# DAU_Kupplung_3phasig_V1_6.net
KiCad netlist of a schematic drawn in EAGLE
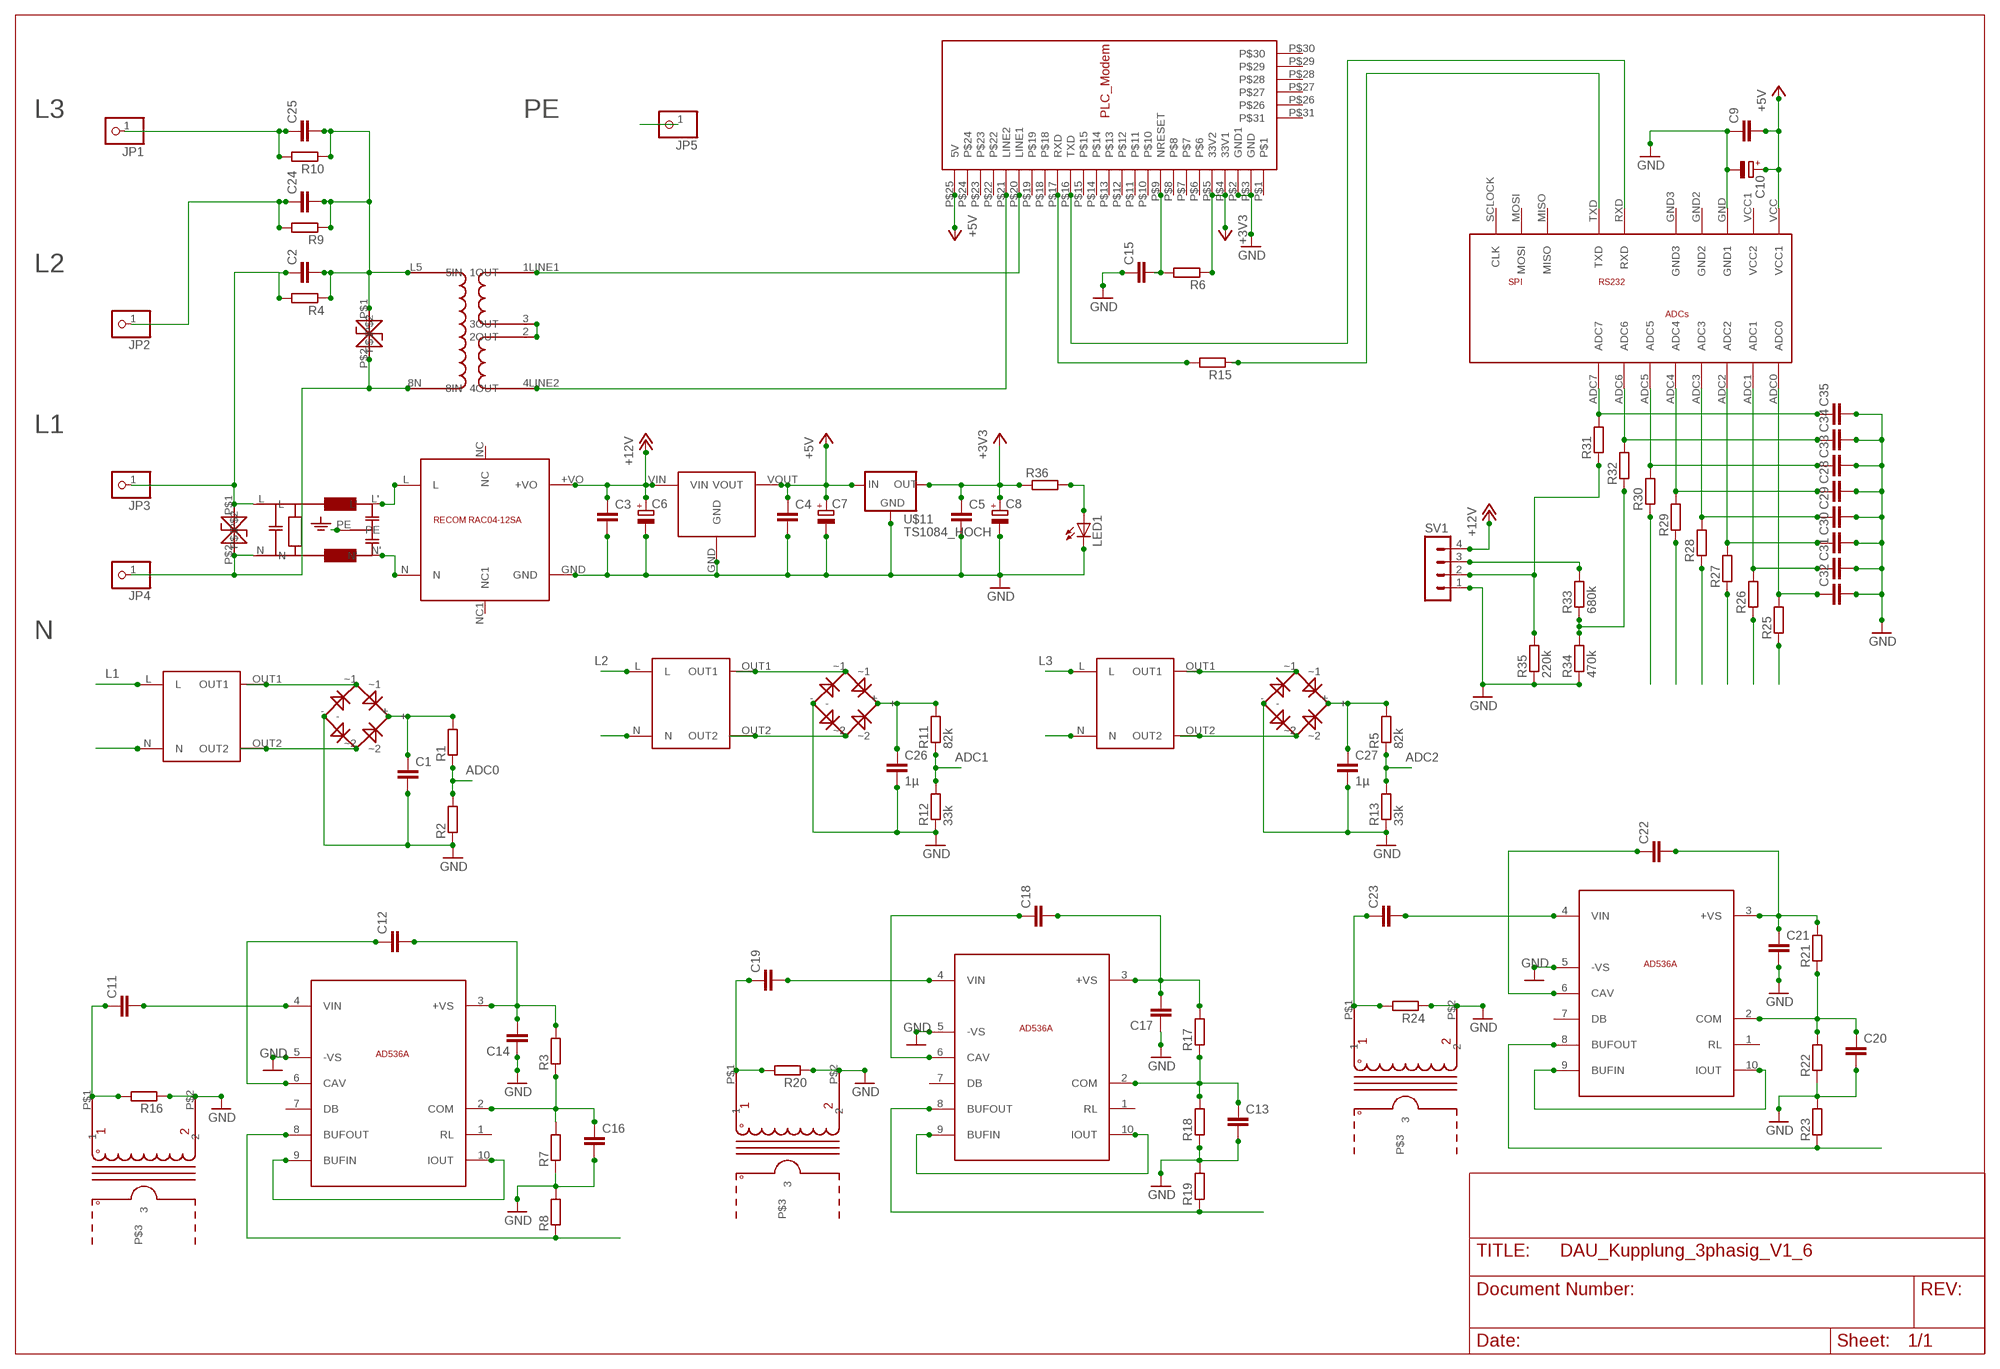
[diagram p0: schematic, sheet 1]

(export (version "E")
  (design (tool "Eeschema 10.0.6"))
  (components
    (comp (ref "AC1002_1")
      (value "AC1010")
      (footprint "eagle-import:AC1010")
      (libsource (lib "eagle-import") (part "AC1010"))
    )
    (comp (ref "C1")
      (value "C-EUC0805K")
      (footprint "eagle-import:C0805K")
      (libsource (lib "eagle-import") (part "C-EUC0805K"))
    )
    (comp (ref "C2")
      (value "C-EU225-087X268")
      (footprint "eagle-import:C225-087X268")
      (libsource (lib "eagle-import") (part "C-EU225-087X268"))
    )
    (comp (ref "C3")
      (value "C-EUC0805K")
      (footprint "eagle-import:C0805K")
      (libsource (lib "eagle-import") (part "C-EUC0805K"))
    )
    (comp (ref "C4")
      (value "C-EUC0805K")
      (footprint "eagle-import:C0805K")
      (libsource (lib "eagle-import") (part "C-EUC0805K"))
    )
    (comp (ref "C5")
      (value "C-EUC0805K")
      (footprint "eagle-import:C0805K")
      (libsource (lib "eagle-import") (part "C-EUC0805K"))
    )
    (comp (ref "C6")
      (value "CPOL-EUE2.5-6")
      (footprint "eagle-import:E2,5-6")
      (libsource (lib "eagle-import") (part "resistor_CPOL-EUE2.5-6"))
    )
    (comp (ref "C7")
      (value "CPOL-EUE2.5-6")
      (footprint "eagle-import:E2,5-6")
      (libsource (lib "eagle-import") (part "resistor_CPOL-EUE2.5-6"))
    )
    (comp (ref "C8")
      (value "CPOL-EUE2.5-6")
      (footprint "eagle-import:E2,5-6")
      (libsource (lib "eagle-import") (part "resistor_CPOL-EUE2.5-6"))
    )
    (comp (ref "C9")
      (value "C-EUC0805K")
      (footprint "eagle-import:C0805K")
      (libsource (lib "eagle-import") (part "C-EUC0805K"))
    )
    (comp (ref "C10")
      (value "CPOL-EUE2,5-6E")
      (footprint "eagle-import:E2,5-6E")
      (libsource (lib "eagle-import") (part "CPOL-EUE2,5-6E"))
    )
    (comp (ref "C11")
      (value "C-EUC0805K")
      (footprint "eagle-import:C0805K")
      (libsource (lib "eagle-import") (part "C-EUC0805K"))
    )
    (comp (ref "C12")
      (value "C-EUC0805K")
      (footprint "eagle-import:C0805K")
      (libsource (lib "eagle-import") (part "C-EUC0805K"))
    )
    (comp (ref "C13")
      (value "C-EUC0805K")
      (footprint "eagle-import:C0805K")
      (libsource (lib "eagle-import") (part "C-EUC0805K"))
    )
    (comp (ref "C14")
      (value "C-EUC0805K")
      (footprint "eagle-import:C0805K")
      (libsource (lib "eagle-import") (part "C-EUC0805K"))
    )
    (comp (ref "C15")
      (value "C-EUC0805K")
      (footprint "eagle-import:C0805K")
      (libsource (lib "eagle-import") (part "C-EUC0805K"))
    )
    (comp (ref "C16")
      (value "C-EUC0805K")
      (footprint "eagle-import:C0805K")
      (libsource (lib "eagle-import") (part "C-EUC0805K"))
    )
    (comp (ref "C17")
      (value "C-EUC0805K")
      (footprint "eagle-import:C0805K")
      (libsource (lib "eagle-import") (part "C-EUC0805K"))
    )
    (comp (ref "C18")
      (value "C-EUC0805K")
      (footprint "eagle-import:C0805K")
      (libsource (lib "eagle-import") (part "C-EUC0805K"))
    )
    (comp (ref "C19")
      (value "C-EUC0805K")
      (footprint "eagle-import:C0805K")
      (libsource (lib "eagle-import") (part "C-EUC0805K"))
    )
    (comp (ref "C20")
      (value "C-EUC0805K")
      (footprint "eagle-import:C0805K")
      (libsource (lib "eagle-import") (part "C-EUC0805K"))
    )
    (comp (ref "C21")
      (value "C-EUC0805K")
      (footprint "eagle-import:C0805K")
      (libsource (lib "eagle-import") (part "C-EUC0805K"))
    )
    (comp (ref "C22")
      (value "C-EUC0805K")
      (footprint "eagle-import:C0805K")
      (libsource (lib "eagle-import") (part "C-EUC0805K"))
    )
    (comp (ref "C23")
      (value "C-EUC0805K")
      (footprint "eagle-import:C0805K")
      (libsource (lib "eagle-import") (part "C-EUC0805K"))
    )
    (comp (ref "C24")
      (value "C-EU225-087X268")
      (footprint "eagle-import:C225-087X268")
      (libsource (lib "eagle-import") (part "C-EU225-087X268"))
    )
    (comp (ref "C25")
      (value "C-EU225-087X268")
      (footprint "eagle-import:C225-087X268")
      (libsource (lib "eagle-import") (part "C-EU225-087X268"))
    )
    (comp (ref "C26")
      (value "1µ")
      (footprint "eagle-import:C0805K")
      (libsource (lib "eagle-import") (part "C-EUC0805K"))
    )
    (comp (ref "C27")
      (value "1µ")
      (footprint "eagle-import:C0805K")
      (libsource (lib "eagle-import") (part "C-EUC0805K"))
    )
    (comp (ref "C28")
      (value "C-EUC0805K")
      (footprint "eagle-import:C0805K")
      (libsource (lib "eagle-import") (part "C-EUC0805K"))
    )
    (comp (ref "C29")
      (value "C-EUC0805K")
      (footprint "eagle-import:C0805K")
      (libsource (lib "eagle-import") (part "C-EUC0805K"))
    )
    (comp (ref "C30")
      (value "C-EUC0805K")
      (footprint "eagle-import:C0805K")
      (libsource (lib "eagle-import") (part "C-EUC0805K"))
    )
    (comp (ref "C31")
      (value "C-EUC0805K")
      (footprint "eagle-import:C0805K")
      (libsource (lib "eagle-import") (part "C-EUC0805K"))
    )
    (comp (ref "C32")
      (value "C-EUC0805K")
      (footprint "eagle-import:C0805K")
      (libsource (lib "eagle-import") (part "C-EUC0805K"))
    )
    (comp (ref "C33")
      (value "C-EUC0805K")
      (footprint "eagle-import:C0805K")
      (libsource (lib "eagle-import") (part "C-EUC0805K"))
    )
    (comp (ref "C34")
      (value "C-EUC0805K")
      (footprint "eagle-import:C0805K")
      (libsource (lib "eagle-import") (part "C-EUC0805K"))
    )
    (comp (ref "C35")
      (value "C-EUC0805K")
      (footprint "eagle-import:C0805K")
      (libsource (lib "eagle-import") (part "C-EUC0805K"))
    )
    (comp (ref "JP1")
      (value "PINHD-1X1")
      (footprint "eagle-import:1X01")
      (libsource (lib "eagle-import") (part "PINHD-1X1"))
    )
    (comp (ref "JP2")
      (value "PINHD-1X1")
      (footprint "eagle-import:1X01")
      (libsource (lib "eagle-import") (part "PINHD-1X1"))
    )
    (comp (ref "JP3")
      (value "PINHD-1X1")
      (footprint "eagle-import:1X01")
      (libsource (lib "eagle-import") (part "PINHD-1X1"))
    )
    (comp (ref "JP4")
      (value "PINHD-1X1")
      (footprint "eagle-import:1X01")
      (libsource (lib "eagle-import") (part "PINHD-1X1"))
    )
    (comp (ref "JP5")
      (value "PINHD-1X1")
      (footprint "eagle-import:1X01")
      (libsource (lib "eagle-import") (part "PINHD-1X1"))
    )
    (comp (ref "LED1")
      (value "LEDSQR2X5")
      (footprint "eagle-import:LED2X5")
      (libsource (lib "eagle-import") (part "LEDSQR2X5"))
    )
    (comp (ref "R1")
      (value "R-EU_R0805")
      (footprint "eagle-import:R0805")
      (libsource (lib "eagle-import") (part "R-EU_R0805"))
    )
    (comp (ref "R2")
      (value "R-EU_R0805")
      (footprint "eagle-import:R0805")
      (libsource (lib "eagle-import") (part "R-EU_R0805"))
    )
    (comp (ref "R3")
      (value "R-EU_R0805")
      (footprint "eagle-import:R0805")
      (libsource (lib "eagle-import") (part "R-EU_R0805"))
    )
    (comp (ref "R4")
      (value "R-EU_0204/7")
      (footprint "eagle-import:0204_7")
      (libsource (lib "eagle-import") (part "R-EU_0204/7"))
    )
    (comp (ref "R5")
      (value "82k")
      (footprint "eagle-import:R0805")
      (libsource (lib "eagle-import") (part "R-EU_R0805"))
    )
    (comp (ref "R6")
      (value "R-EU_R0805")
      (footprint "eagle-import:R0805")
      (libsource (lib "eagle-import") (part "R-EU_R0805"))
    )
    (comp (ref "R7")
      (value "R-EU_R0805")
      (footprint "eagle-import:R0805")
      (libsource (lib "eagle-import") (part "R-EU_R0805"))
    )
    (comp (ref "R8")
      (value "R-EU_R0805")
      (footprint "eagle-import:R0805")
      (libsource (lib "eagle-import") (part "R-EU_R0805"))
    )
    (comp (ref "R9")
      (value "R-EU_0204/7")
      (footprint "eagle-import:0204_7")
      (libsource (lib "eagle-import") (part "R-EU_0204/7"))
    )
    (comp (ref "R10")
      (value "R-EU_0204/7")
      (footprint "eagle-import:0204_7")
      (libsource (lib "eagle-import") (part "R-EU_0204/7"))
    )
    (comp (ref "R11")
      (value "82k")
      (footprint "eagle-import:R0805")
      (libsource (lib "eagle-import") (part "R-EU_R0805"))
    )
    (comp (ref "R12")
      (value "33k")
      (footprint "eagle-import:R0805")
      (libsource (lib "eagle-import") (part "R-EU_R0805"))
    )
    (comp (ref "R13")
      (value "33k")
      (footprint "eagle-import:R0805")
      (libsource (lib "eagle-import") (part "R-EU_R0805"))
    )
    (comp (ref "R15")
      (value "R-EU_R0805")
      (footprint "eagle-import:R0805")
      (libsource (lib "eagle-import") (part "R-EU_R0805"))
    )
    (comp (ref "R16")
      (value "R-EU_0204/7")
      (footprint "eagle-import:0204_7")
      (libsource (lib "eagle-import") (part "R-EU_0204/7"))
    )
    (comp (ref "R17")
      (value "R-EU_R0805")
      (footprint "eagle-import:R0805")
      (libsource (lib "eagle-import") (part "R-EU_R0805"))
    )
    (comp (ref "R18")
      (value "R-EU_R0805")
      (footprint "eagle-import:R0805")
      (libsource (lib "eagle-import") (part "R-EU_R0805"))
    )
    (comp (ref "R19")
      (value "R-EU_R0805")
      (footprint "eagle-import:R0805")
      (libsource (lib "eagle-import") (part "R-EU_R0805"))
    )
    (comp (ref "R20")
      (value "R-EU_0204/7")
      (footprint "eagle-import:0204_7")
      (libsource (lib "eagle-import") (part "R-EU_0204/7"))
    )
    (comp (ref "R21")
      (value "R-EU_R0805")
      (footprint "eagle-import:R0805")
      (libsource (lib "eagle-import") (part "R-EU_R0805"))
    )
    (comp (ref "R22")
      (value "R-EU_R0805")
      (footprint "eagle-import:R0805")
      (libsource (lib "eagle-import") (part "R-EU_R0805"))
    )
    (comp (ref "R23")
      (value "R-EU_R0805")
      (footprint "eagle-import:R0805")
      (libsource (lib "eagle-import") (part "R-EU_R0805"))
    )
    (comp (ref "R24")
      (value "R-EU_0204/7")
      (footprint "eagle-import:0204_7")
      (libsource (lib "eagle-import") (part "R-EU_0204/7"))
    )
    (comp (ref "R25")
      (value "R-EU_R0805")
      (footprint "eagle-import:R0805")
      (libsource (lib "eagle-import") (part "R-EU_R0805"))
    )
    (comp (ref "R26")
      (value "R-EU_R0805")
      (footprint "eagle-import:R0805")
      (libsource (lib "eagle-import") (part "R-EU_R0805"))
    )
    (comp (ref "R27")
      (value "R-EU_R0805")
      (footprint "eagle-import:R0805")
      (libsource (lib "eagle-import") (part "R-EU_R0805"))
    )
    (comp (ref "R28")
      (value "R-EU_R0805")
      (footprint "eagle-import:R0805")
      (libsource (lib "eagle-import") (part "R-EU_R0805"))
    )
    (comp (ref "R29")
      (value "R-EU_R0805")
      (footprint "eagle-import:R0805")
      (libsource (lib "eagle-import") (part "R-EU_R0805"))
    )
    (comp (ref "R30")
      (value "R-EU_R0805")
      (footprint "eagle-import:R0805")
      (libsource (lib "eagle-import") (part "R-EU_R0805"))
    )
    (comp (ref "R31")
      (value "R-EU_R0805")
      (footprint "eagle-import:R0805")
      (libsource (lib "eagle-import") (part "R-EU_R0805"))
    )
    (comp (ref "R32")
      (value "R-EU_R0805")
      (footprint "eagle-import:R0805")
      (libsource (lib "eagle-import") (part "R-EU_R0805"))
    )
    (comp (ref "R33")
      (value "680k")
      (footprint "eagle-import:R0805")
      (libsource (lib "eagle-import") (part "R-EU_R0805"))
    )
    (comp (ref "R34")
      (value "470k")
      (footprint "eagle-import:R0805")
      (libsource (lib "eagle-import") (part "R-EU_R0805"))
    )
    (comp (ref "R35")
      (value "220k")
      (footprint "eagle-import:R0805")
      (libsource (lib "eagle-import") (part "R-EU_R0805"))
    )
    (comp (ref "R36")
      (value "R-EU_R0805")
      (footprint "eagle-import:R0805")
      (libsource (lib "eagle-import") (part "R-EU_R0805"))
    )
    (comp (ref "SV1")
      (value "MA04-1")
      (footprint "eagle-import:MA04-1")
      (libsource (lib "eagle-import") (part "MA04-1"))
    )
    (comp (ref "TSV1")
      (value "TSV")
      (footprint "eagle-import:TSV")
      (libsource (lib "eagle-import") (part "TSV"))
    )
    (comp (ref "TSV2")
      (value "TSV")
      (footprint "eagle-import:TSV")
      (libsource (lib "eagle-import") (part "TSV"))
    )
    (comp (ref "U$1")
      (value "RECOM_RAC04_12SA")
      (footprint "eagle-import:RAC04_12SA")
      (libsource (lib "eagle-import") (part "RECOM_RAC04_12SA"))
    )
    (comp (ref "U$2")
      (value "SICHERHEITSTRAFO")
      (footprint "eagle-import:TRAFO_0,35VA")
      (libsource (lib "eagle-import") (part "SICHERHEITSTRAFO"))
    )
    (comp (ref "U$3")
      (value "ADUC831_MINIMUM")
      (footprint "eagle-import:ADUC_MINIMUM")
      (libsource (lib "eagle-import") (part "ADUC831_MINIMUM"))
    )
    (comp (ref "U$4")
      (value "MODEMSTECKER")
      (footprint "eagle-import:MODEM_FUSS")
      (libsource (lib "eagle-import") (part "MODEMSTECKER"))
    )
    (comp (ref "U$5")
      (value "PLC_UEBERTRAGER_V2")
      (footprint "eagle-import:PLC-UEBERTRAGER_V2")
      (libsource (lib "eagle-import") (part "PLC_UEBERTRAGER_V2"))
    )
    (comp (ref "U$7")
      (value "AC1010")
      (footprint "eagle-import:AC1010")
      (libsource (lib "eagle-import") (part "AC1010"))
    )
    (comp (ref "U$8")
      (value "RECTIFIER")
      (footprint "eagle-import:RECTIFIER")
      (libsource (lib "eagle-import") (part "RECTIFIER"))
    )
    (comp (ref "U$10")
      (value "RECOM_785_05")
      (footprint "eagle-import:RECOM785X")
      (libsource (lib "eagle-import") (part "RECOM_785_05"))
    )
    (comp (ref "U$11")
      (value "TS1084_HOCH")
      (footprint "eagle-import:TS1084_HOCH")
      (libsource (lib "eagle-import") (part "TS1084_HOCH"))
    )
    (comp (ref "U$12")
      (value "AD536")
      (footprint "eagle-import:TO100_10PIN")
      (libsource (lib "eagle-import") (part "AD536"))
    )
    (comp (ref "U$13")
      (value "AD536")
      (footprint "eagle-import:TO100_10PIN")
      (libsource (lib "eagle-import") (part "AD536"))
    )
    (comp (ref "U$14")
      (value "AC1010")
      (footprint "eagle-import:AC1010")
      (libsource (lib "eagle-import") (part "AC1010"))
    )
    (comp (ref "U$15")
      (value "AD536")
      (footprint "eagle-import:TO100_10PIN")
      (libsource (lib "eagle-import") (part "AD536"))
    )
    (comp (ref "U$16")
      (value "SICHERHEITSTRAFO")
      (footprint "eagle-import:TRAFO_0,35VA")
      (libsource (lib "eagle-import") (part "SICHERHEITSTRAFO"))
    )
    (comp (ref "U$17")
      (value "RECTIFIER")
      (footprint "eagle-import:RECTIFIER")
      (libsource (lib "eagle-import") (part "RECTIFIER"))
    )
    (comp (ref "U$18")
      (value "SICHERHEITSTRAFO")
      (footprint "eagle-import:TRAFO_0,35VA")
      (libsource (lib "eagle-import") (part "SICHERHEITSTRAFO"))
    )
    (comp (ref "U$19")
      (value "RECTIFIER")
      (footprint "eagle-import:RECTIFIER")
      (libsource (lib "eagle-import") (part "RECTIFIER"))
    )
    (comp (ref "U$20")
      (value "NETZFILTER_05_A")
      (footprint "eagle-import:NETZFILTER")
      (libsource (lib "eagle-import") (part "NETZFILTER_05_A"))
    )
  )
  (nets
    (net (code "1") (name "+3V3") (class "Default")
      (node (ref "C5") (pin "1") (pinfunction "1_1") (pintype "passive"))
      (node (ref "C8") (pin "+") (pinfunction "+_+") (pintype "passive"))
      (node (ref "R36") (pin "1") (pinfunction "1_1") (pintype "passive"))
      (node (ref "R6") (pin "1") (pinfunction "1_1") (pintype "passive"))
      (node (ref "U$11") (pin "OUT") (pinfunction "OUT_OUT") (pintype "passive"))
      (node (ref "U$4") (pin "P$4") (pinfunction "33V1_P$4") (pintype "bidirectional"))
      (node (ref "U$4") (pin "P$5") (pinfunction "33V2_P$5") (pintype "bidirectional"))
    )
    (net (code "2") (name "+5V") (class "Default")
      (node (ref "C10") (pin "+") (pinfunction "+_+") (pintype "passive"))
      (node (ref "C4") (pin "1") (pinfunction "1_1") (pintype "passive"))
      (node (ref "C7") (pin "+") (pinfunction "+_+") (pintype "passive"))
      (node (ref "C9") (pin "2") (pinfunction "2_2") (pintype "passive"))
      (node (ref "U$10") (pin "VOUT") (pinfunction "VOUT_VOUT") (pintype "bidirectional"))
      (node (ref "U$11") (pin "IN") (pinfunction "IN_IN") (pintype "input"))
      (node (ref "U$3") (pin "VCC") (pinfunction "VCC1_VCC") (pintype "bidirectional"))
      (node (ref "U$4") (pin "P$25") (pinfunction "5V_P$25") (pintype "bidirectional"))
    )
    (net (code "3") (name "+12V") (class "Default")
      (node (ref "C3") (pin "1") (pinfunction "1_1") (pintype "passive"))
      (node (ref "C6") (pin "+") (pinfunction "+_+") (pintype "passive"))
      (node (ref "SV1") (pin "4") (pinfunction "4_4") (pintype "passive"))
      (node (ref "U$1") (pin "+VO") (pinfunction "+VO_+VO") (pintype "bidirectional"))
      (node (ref "U$10") (pin "VIN") (pinfunction "VIN_VIN") (pintype "bidirectional"))
    )
    (net (code "4") (name "/I1") (class "Default")
      (node (ref "R28") (pin "1") (pinfunction "1_1") (pintype "passive"))
      (node (ref "R8") (pin "1") (pinfunction "1_1") (pintype "passive"))
      (node (ref "U$13") (pin "8") (pinfunction "BUFOUT_8") (pintype "bidirectional"))
    )
    (net (code "5") (name "/I2") (class "Default")
      (node (ref "R19") (pin "1") (pinfunction "1_1") (pintype "passive"))
      (node (ref "R29") (pin "1") (pinfunction "1_1") (pintype "passive"))
      (node (ref "U$12") (pin "8") (pinfunction "BUFOUT_8") (pintype "bidirectional"))
    )
    (net (code "6") (name "/I3") (class "Default")
      (node (ref "R23") (pin "1") (pinfunction "1_1") (pintype "passive"))
      (node (ref "R30") (pin "1") (pinfunction "1_1") (pintype "passive"))
      (node (ref "U$15") (pin "8") (pinfunction "BUFOUT_8") (pintype "bidirectional"))
    )
    (net (code "7") (name "/L1") (class "Default")
      (node (ref "C2") (pin "1") (pinfunction "1_1") (pintype "passive"))
      (node (ref "JP3") (pin "1") (pinfunction "1_1") (pintype "passive"))
      (node (ref "R4") (pin "2") (pinfunction "2_2") (pintype "passive"))
      (node (ref "TSV1") (pin "P$1") (pinfunction "P$1_P$1") (pintype "bidirectional"))
      (node (ref "U$2") (pin "L") (pinfunction "L_L") (pintype "bidirectional"))
      (node (ref "U$20") (pin "L") (pinfunction "L_L") (pintype "bidirectional"))
    )
    (net (code "8") (name "/L2") (class "Default")
      (node (ref "C24") (pin "1") (pinfunction "1_1") (pintype "passive"))
      (node (ref "JP2") (pin "1") (pinfunction "1_1") (pintype "passive"))
      (node (ref "R9") (pin "2") (pinfunction "2_2") (pintype "passive"))
      (node (ref "U$16") (pin "L") (pinfunction "L_L") (pintype "bidirectional"))
    )
    (net (code "9") (name "/L3") (class "Default")
      (node (ref "C25") (pin "1") (pinfunction "1_1") (pintype "passive"))
      (node (ref "JP1") (pin "1") (pinfunction "1_1") (pintype "passive"))
      (node (ref "R10") (pin "2") (pinfunction "2_2") (pintype "passive"))
      (node (ref "U$18") (pin "L") (pinfunction "L_L") (pintype "bidirectional"))
    )
    (net (code "10") (name "/N") (class "Default")
      (node (ref "JP4") (pin "1") (pinfunction "1_1") (pintype "passive"))
      (node (ref "TSV1") (pin "P$2") (pinfunction "P$2_P$2") (pintype "bidirectional"))
      (node (ref "TSV2") (pin "P$2") (pinfunction "P$2_P$2") (pintype "bidirectional"))
      (node (ref "U$16") (pin "N") (pinfunction "N_N") (pintype "bidirectional"))
      (node (ref "U$18") (pin "N") (pinfunction "N_N") (pintype "bidirectional"))
      (node (ref "U$2") (pin "N") (pinfunction "N_N") (pintype "bidirectional"))
      (node (ref "U$20") (pin "N") (pinfunction "N_N") (pintype "bidirectional"))
      (node (ref "U$5") (pin "8N") (pinfunction "8IN_8N") (pintype "input"))
    )
    (net (code "11") (name "/PE") (class "Default")
      (node (ref "JP5") (pin "1") (pinfunction "1_1") (pintype "passive"))
      (node (ref "U$20") (pin "PE") (pinfunction "PE_PE") (pintype "input"))
    )
    (net (code "12") (name "/U1") (class "Default")
      (node (ref "R1") (pin "1") (pinfunction "1_1") (pintype "passive"))
      (node (ref "R2") (pin "2") (pinfunction "2_2") (pintype "passive"))
      (node (ref "R25") (pin "1") (pinfunction "1_1") (pintype "passive"))
    )
    (net (code "13") (name "/U2") (class "Default")
      (node (ref "R11") (pin "1") (pinfunction "1_1") (pintype "passive"))
      (node (ref "R12") (pin "2") (pinfunction "2_2") (pintype "passive"))
      (node (ref "R26") (pin "1") (pinfunction "1_1") (pintype "passive"))
    )
    (net (code "14") (name "/U3") (class "Default")
      (node (ref "R13") (pin "2") (pinfunction "2_2") (pintype "passive"))
      (node (ref "R27") (pin "1") (pinfunction "1_1") (pintype "passive"))
      (node (ref "R5") (pin "1") (pinfunction "1_1") (pintype "passive"))
    )
    (net (code "15") (name "GND") (class "Default")
      (node (ref "AC1002_1") (pin "P$2") (pinfunction "2_P$2") (pintype "output"))
      (node (ref "C1") (pin "2") (pinfunction "2_2") (pintype "passive"))
      (node (ref "C10") (pin "-") (pinfunction "-_-") (pintype "passive"))
      (node (ref "C13") (pin "2") (pinfunction "2_2") (pintype "passive"))
      (node (ref "C14") (pin "1") (pinfunction "1_1") (pintype "passive"))
      (node (ref "C15") (pin "1") (pinfunction "1_1") (pintype "passive"))
      (node (ref "C16") (pin "2") (pinfunction "2_2") (pintype "passive"))
      (node (ref "C17") (pin "1") (pinfunction "1_1") (pintype "passive"))
      (node (ref "C20") (pin "2") (pinfunction "2_2") (pintype "passive"))
      (node (ref "C21") (pin "2") (pinfunction "2_2") (pintype "passive"))
      (node (ref "C26") (pin "2") (pinfunction "2_2") (pintype "passive"))
      (node (ref "C27") (pin "2") (pinfunction "2_2") (pintype "passive"))
      (node (ref "C28") (pin "2") (pinfunction "2_2") (pintype "passive"))
      (node (ref "C29") (pin "2") (pinfunction "2_2") (pintype "passive"))
      (node (ref "C3") (pin "2") (pinfunction "2_2") (pintype "passive"))
      (node (ref "C30") (pin "2") (pinfunction "2_2") (pintype "passive"))
      (node (ref "C31") (pin "2") (pinfunction "2_2") (pintype "passive"))
      (node (ref "C32") (pin "2") (pinfunction "2_2") (pintype "passive"))
      (node (ref "C33") (pin "2") (pinfunction "2_2") (pintype "passive"))
      (node (ref "C34") (pin "2") (pinfunction "2_2") (pintype "passive"))
      (node (ref "C35") (pin "2") (pinfunction "2_2") (pintype "passive"))
      (node (ref "C4") (pin "2") (pinfunction "2_2") (pintype "passive"))
      (node (ref "C5") (pin "2") (pinfunction "2_2") (pintype "passive"))
      (node (ref "C6") (pin "-") (pinfunction "-_-") (pintype "passive"))
      (node (ref "C7") (pin "-") (pinfunction "-_-") (pintype "passive"))
      (node (ref "C8") (pin "-") (pinfunction "-_-") (pintype "passive"))
      (node (ref "C9") (pin "1") (pinfunction "1_1") (pintype "passive"))
      (node (ref "LED1") (pin "K") (pinfunction "C_K") (pintype "passive"))
      (node (ref "R12") (pin "1") (pinfunction "1_1") (pintype "passive"))
      (node (ref "R13") (pin "1") (pinfunction "1_1") (pintype "passive"))
      (node (ref "R16") (pin "1") (pinfunction "1_1") (pintype "passive"))
      (node (ref "R18") (pin "1") (pinfunction "1_1") (pintype "passive"))
      (node (ref "R19") (pin "2") (pinfunction "2_2") (pintype "passive"))
      (node (ref "R2") (pin "1") (pinfunction "1_1") (pintype "passive"))
      (node (ref "R20") (pin "1") (pinfunction "1_1") (pintype "passive"))
      (node (ref "R22") (pin "1") (pinfunction "1_1") (pintype "passive"))
      (node (ref "R23") (pin "2") (pinfunction "2_2") (pintype "passive"))
      (node (ref "R24") (pin "1") (pinfunction "1_1") (pintype "passive"))
      (node (ref "R34") (pin "1") (pinfunction "1_1") (pintype "passive"))
      (node (ref "R35") (pin "1") (pinfunction "1_1") (pintype "passive"))
      (node (ref "R7") (pin "1") (pinfunction "1_1") (pintype "passive"))
      (node (ref "R8") (pin "2") (pinfunction "2_2") (pintype "passive"))
      (node (ref "SV1") (pin "1") (pinfunction "1_1") (pintype "passive"))
      (node (ref "U$1") (pin "GND") (pinfunction "GND_GND") (pintype "bidirectional"))
      (node (ref "U$10") (pin "GND") (pinfunction "GND_GND") (pintype "bidirectional"))
      (node (ref "U$11") (pin "GND") (pinfunction "GND_GND") (pintype "input"))
      (node (ref "U$12") (pin "5") (pinfunction "-VS_5") (pintype "bidirectional"))
      (node (ref "U$13") (pin "5") (pinfunction "-VS_5") (pintype "bidirectional"))
      (node (ref "U$14") (pin "P$2") (pinfunction "2_P$2") (pintype "output"))
      (node (ref "U$15") (pin "5") (pinfunction "-VS_5") (pintype "bidirectional"))
      (node (ref "U$17") (pin "-") (pinfunction "-_-") (pintype "bidirectional"))
      (node (ref "U$19") (pin "-") (pinfunction "-_-") (pintype "bidirectional"))
      (node (ref "U$3") (pin "GND") (pinfunction "GND1_GND") (pintype "bidirectional"))
      (node (ref "U$4") (pin "P$2") (pinfunction "GND1_P$2") (pintype "bidirectional"))
      (node (ref "U$4") (pin "P$3") (pinfunction "GND_P$3") (pintype "bidirectional"))
      (node (ref "U$7") (pin "P$2") (pinfunction "2_P$2") (pintype "output"))
      (node (ref "U$8") (pin "-") (pinfunction "-_-") (pintype "bidirectional"))
    )
    (net (code "16") (name "Net-(AC1002_1-1)") (class "Default")
      (node (ref "AC1002_1") (pin "P$1") (pinfunction "1_P$1") (pintype "output"))
      (node (ref "C11") (pin "1") (pinfunction "1_1") (pintype "passive"))
      (node (ref "R16") (pin "2") (pinfunction "2_2") (pintype "passive"))
    )
    (net (code "17") (name "Net-(C1-Pad1)") (class "Default")
      (node (ref "C1") (pin "1") (pinfunction "1_1") (pintype "passive"))
      (node (ref "R1") (pin "2") (pinfunction "2_2") (pintype "passive"))
      (node (ref "U$8") (pin "+") (pinfunction "+_+") (pintype "bidirectional"))
    )
    (net (code "18") (name "Net-(C26-Pad1)") (class "Default")
      (node (ref "C26") (pin "1") (pinfunction "1_1") (pintype "passive"))
      (node (ref "R11") (pin "2") (pinfunction "2_2") (pintype "passive"))
      (node (ref "U$17") (pin "+") (pinfunction "+_+") (pintype "bidirectional"))
    )
    (net (code "19") (name "Net-(C27-Pad1)") (class "Default")
      (node (ref "C27") (pin "1") (pinfunction "1_1") (pintype "passive"))
      (node (ref "R5") (pin "2") (pinfunction "2_2") (pintype "passive"))
      (node (ref "U$19") (pin "+") (pinfunction "+_+") (pintype "bidirectional"))
    )
    (net (code "20") (name "Net-(C28-Pad1)") (class "Default")
      (node (ref "C28") (pin "1") (pinfunction "1_1") (pintype "passive"))
      (node (ref "R29") (pin "2") (pinfunction "2_2") (pintype "passive"))
      (node (ref "U$3") (pin "ADC4") (pinfunction "ADC4_ADC4") (pintype "bidirectional"))
    )
    (net (code "21") (name "Net-(C29-Pad1)") (class "Default")
      (node (ref "C29") (pin "1") (pinfunction "1_1") (pintype "passive"))
      (node (ref "R28") (pin "2") (pinfunction "2_2") (pintype "passive"))
      (node (ref "U$3") (pin "ADC3") (pinfunction "ADC3_ADC3") (pintype "bidirectional"))
    )
    (net (code "22") (name "Net-(C30-Pad1)") (class "Default")
      (node (ref "C30") (pin "1") (pinfunction "1_1") (pintype "passive"))
      (node (ref "R27") (pin "2") (pinfunction "2_2") (pintype "passive"))
      (node (ref "U$3") (pin "ADC2") (pinfunction "ADC2_ADC2") (pintype "bidirectional"))
    )
    (net (code "23") (name "Net-(C31-Pad1)") (class "Default")
      (node (ref "C31") (pin "1") (pinfunction "1_1") (pintype "passive"))
      (node (ref "R26") (pin "2") (pinfunction "2_2") (pintype "passive"))
      (node (ref "U$3") (pin "ADC1") (pinfunction "ADC1_ADC1") (pintype "bidirectional"))
    )
    (net (code "24") (name "Net-(C32-Pad1)") (class "Default")
      (node (ref "C32") (pin "1") (pinfunction "1_1") (pintype "passive"))
      (node (ref "R25") (pin "2") (pinfunction "2_2") (pintype "passive"))
      (node (ref "U$3") (pin "ADC0") (pinfunction "ADC0_ADC0") (pintype "bidirectional"))
    )
    (net (code "25") (name "Net-(C33-Pad1)") (class "Default")
      (node (ref "C33") (pin "1") (pinfunction "1_1") (pintype "passive"))
      (node (ref "R30") (pin "2") (pinfunction "2_2") (pintype "passive"))
      (node (ref "U$3") (pin "ADC5") (pinfunction "ADC5_ADC5") (pintype "bidirectional"))
    )
    (net (code "26") (name "Net-(C34-Pad1)") (class "Default")
      (node (ref "C34") (pin "1") (pinfunction "1_1") (pintype "passive"))
      (node (ref "R32") (pin "2") (pinfunction "2_2") (pintype "passive"))
      (node (ref "U$3") (pin "ADC6") (pinfunction "ADC6_ADC6") (pintype "bidirectional"))
    )
    (net (code "27") (name "Net-(C35-Pad1)") (class "Default")
      (node (ref "C35") (pin "1") (pinfunction "1_1") (pintype "passive"))
      (node (ref "R31") (pin "2") (pinfunction "2_2") (pintype "passive"))
      (node (ref "U$3") (pin "ADC7") (pinfunction "ADC7_ADC7") (pintype "bidirectional"))
    )
    (net (code "28") (name "Net-(LED1-PadA)") (class "Default")
      (node (ref "LED1") (pin "A") (pinfunction "A_A") (pintype "passive"))
      (node (ref "R36") (pin "2") (pinfunction "2_2") (pintype "passive"))
    )
    (net (code "29") (name "Net-(R15-Pad1)") (class "Default")
      (node (ref "R15") (pin "1") (pinfunction "1_1") (pintype "passive"))
      (node (ref "U$3") (pin "TXD") (pinfunction "TXD_TXD") (pintype "bidirectional"))
    )
    (net (code "30") (name "Net-(R31-Pad1)") (class "Default")
      (node (ref "R31") (pin "1") (pinfunction "1_1") (pintype "passive"))
      (node (ref "R35") (pin "2") (pinfunction "2_2") (pintype "passive"))
      (node (ref "SV1") (pin "2") (pinfunction "2_2") (pintype "passive"))
    )
    (net (code "31") (name "Net-(R32-Pad1)") (class "Default")
      (node (ref "R32") (pin "1") (pinfunction "1_1") (pintype "passive"))
      (node (ref "R33") (pin "1") (pinfunction "1_1") (pintype "passive"))
      (node (ref "R34") (pin "2") (pinfunction "2_2") (pintype "passive"))
    )
    (net (code "32") (name "Net-(R33-Pad2)") (class "Default")
      (node (ref "R33") (pin "2") (pinfunction "2_2") (pintype "passive"))
      (node (ref "SV1") (pin "3") (pinfunction "3_3") (pintype "passive"))
    )
    (net (code "33") (name "Net-(U$1-PadL)") (class "Default")
      (node (ref "U$1") (pin "L") (pinfunction "L_L") (pintype "bidirectional"))
      (node (ref "U$20") (pin "L'") (pinfunction "L'_L'") (pintype "bidirectional"))
    )
    (net (code "34") (name "Net-(U$1-PadN)") (class "Default")
      (node (ref "U$1") (pin "N") (pinfunction "N_N") (pintype "bidirectional"))
      (node (ref "U$20") (pin "N'") (pinfunction "N'_N'") (pintype "bidirectional"))
    )
    (net (code "35") (name "Net-(U$4-LINE1)") (class "Default")
      (node (ref "U$4") (pin "P$20") (pinfunction "LINE1_P$20") (pintype "bidirectional"))
      (node (ref "U$5") (pin "1LINE1") (pinfunction "1OUT_1LINE1") (pintype "output"))
    )
    (net (code "36") (name "Net-(U$4-LINE2)") (class "Default")
      (node (ref "U$4") (pin "P$21") (pinfunction "LINE2_P$21") (pintype "bidirectional"))
      (node (ref "U$5") (pin "4LINE2") (pinfunction "4OUT_4LINE2") (pintype "output"))
    )
    (net (code "37") (name "Net-(U$4-NRESET)") (class "Default")
      (node (ref "C15") (pin "2") (pinfunction "2_2") (pintype "passive"))
      (node (ref "R6") (pin "2") (pinfunction "2_2") (pintype "passive"))
      (node (ref "U$4") (pin "P$9") (pinfunction "NRESET_P$9") (pintype "bidirectional"))
    )
    (net (code "38") (name "Net-(U$4-RXD)") (class "Default")
      (node (ref "R15") (pin "2") (pinfunction "2_2") (pintype "passive"))
      (node (ref "U$4") (pin "P$17") (pinfunction "RXD_P$17") (pintype "bidirectional"))
    )
    (net (code "39") (name "Net-(U$4-TXD)") (class "Default")
      (node (ref "U$3") (pin "RXD") (pinfunction "RXD_RXD") (pintype "bidirectional"))
      (node (ref "U$4") (pin "P$16") (pinfunction "TXD_P$16") (pintype "bidirectional"))
    )
    (net (code "40") (name "Net-(U$5-2OUT)") (class "Default")
      (node (ref "U$5") (pin "2") (pinfunction "2OUT_2") (pintype "output"))
      (node (ref "U$5") (pin "3") (pinfunction "3OUT_3") (pintype "output"))
    )
    (net (code "41") (name "Net-(U$5-5IN)") (class "Default")
      (node (ref "C2") (pin "2") (pinfunction "2_2") (pintype "passive"))
      (node (ref "C24") (pin "2") (pinfunction "2_2") (pintype "passive"))
      (node (ref "C25") (pin "2") (pinfunction "2_2") (pintype "passive"))
      (node (ref "R10") (pin "1") (pinfunction "1_1") (pintype "passive"))
      (node (ref "R4") (pin "1") (pinfunction "1_1") (pintype "passive"))
      (node (ref "R9") (pin "1") (pinfunction "1_1") (pintype "passive"))
      (node (ref "TSV2") (pin "P$1") (pinfunction "P$1_P$1") (pintype "bidirectional"))
      (node (ref "U$5") (pin "L5") (pinfunction "5IN_L5") (pintype "input"))
    )
    (net (code "42") (name "Net-(U$7-1)") (class "Default")
      (node (ref "C19") (pin "1") (pinfunction "1_1") (pintype "passive"))
      (node (ref "R20") (pin "2") (pinfunction "2_2") (pintype "passive"))
      (node (ref "U$7") (pin "P$1") (pinfunction "1_P$1") (pintype "output"))
    )
    (net (code "43") (name "Net-(U$8-~{1})") (class "Default")
      (node (ref "U$2") (pin "OUT1") (pinfunction "OUT1_OUT1") (pintype "bidirectional"))
      (node (ref "U$8") (pin "~1") (pinfunction "~{1}_~1") (pintype "bidirectional"))
    )
    (net (code "44") (name "Net-(U$8-~{2})") (class "Default")
      (node (ref "U$2") (pin "OUT2") (pinfunction "OUT2_OUT2") (pintype "bidirectional"))
      (node (ref "U$8") (pin "~2") (pinfunction "~{2}_~2") (pintype "bidirectional"))
    )
    (net (code "45") (name "Net-(U$12-+VS)") (class "Default")
      (node (ref "C17") (pin "2") (pinfunction "2_2") (pintype "passive"))
      (node (ref "C18") (pin "2") (pinfunction "2_2") (pintype "passive"))
      (node (ref "R17") (pin "2") (pinfunction "2_2") (pintype "passive"))
      (node (ref "U$12") (pin "3") (pinfunction "+VS_3") (pintype "bidirectional"))
    )
    (net (code "46") (name "Net-(U$12-BUFIN)") (class "Default")
      (node (ref "U$12") (pin "10") (pinfunction "IOUT_10") (pintype "bidirectional"))
      (node (ref "U$12") (pin "9") (pinfunction "BUFIN_9") (pintype "bidirectional"))
    )
    (net (code "47") (name "Net-(U$12-CAV)") (class "Default")
      (node (ref "C18") (pin "1") (pinfunction "1_1") (pintype "passive"))
      (node (ref "U$12") (pin "6") (pinfunction "CAV_6") (pintype "bidirectional"))
    )
    (net (code "48") (name "Net-(U$12-COM)") (class "Default")
      (node (ref "C13") (pin "1") (pinfunction "1_1") (pintype "passive"))
      (node (ref "R17") (pin "1") (pinfunction "1_1") (pintype "passive"))
      (node (ref "R18") (pin "2") (pinfunction "2_2") (pintype "passive"))
      (node (ref "U$12") (pin "2") (pinfunction "COM_2") (pintype "bidirectional"))
    )
    (net (code "49") (name "Net-(U$12-VIN)") (class "Default")
      (node (ref "C19") (pin "2") (pinfunction "2_2") (pintype "passive"))
      (node (ref "U$12") (pin "4") (pinfunction "VIN_4") (pintype "bidirectional"))
    )
    (net (code "50") (name "Net-(U$13-+VS)") (class "Default")
      (node (ref "C12") (pin "2") (pinfunction "2_2") (pintype "passive"))
      (node (ref "C14") (pin "2") (pinfunction "2_2") (pintype "passive"))
      (node (ref "R3") (pin "2") (pinfunction "2_2") (pintype "passive"))
      (node (ref "U$13") (pin "3") (pinfunction "+VS_3") (pintype "bidirectional"))
    )
    (net (code "51") (name "Net-(U$13-BUFIN)") (class "Default")
      (node (ref "U$13") (pin "10") (pinfunction "IOUT_10") (pintype "bidirectional"))
      (node (ref "U$13") (pin "9") (pinfunction "BUFIN_9") (pintype "bidirectional"))
    )
    (net (code "52") (name "Net-(U$13-CAV)") (class "Default")
      (node (ref "C12") (pin "1") (pinfunction "1_1") (pintype "passive"))
      (node (ref "U$13") (pin "6") (pinfunction "CAV_6") (pintype "bidirectional"))
    )
    (net (code "53") (name "Net-(U$13-COM)") (class "Default")
      (node (ref "C16") (pin "1") (pinfunction "1_1") (pintype "passive"))
      (node (ref "R3") (pin "1") (pinfunction "1_1") (pintype "passive"))
      (node (ref "R7") (pin "2") (pinfunction "2_2") (pintype "passive"))
      (node (ref "U$13") (pin "2") (pinfunction "COM_2") (pintype "bidirectional"))
    )
    (net (code "54") (name "Net-(U$13-VIN)") (class "Default")
      (node (ref "C11") (pin "2") (pinfunction "2_2") (pintype "passive"))
      (node (ref "U$13") (pin "4") (pinfunction "VIN_4") (pintype "bidirectional"))
    )
    (net (code "55") (name "Net-(U$14-1)") (class "Default")
      (node (ref "C23") (pin "1") (pinfunction "1_1") (pintype "passive"))
      (node (ref "R24") (pin "2") (pinfunction "2_2") (pintype "passive"))
      (node (ref "U$14") (pin "P$1") (pinfunction "1_P$1") (pintype "output"))
    )
    (net (code "56") (name "Net-(U$15-+VS)") (class "Default")
      (node (ref "C21") (pin "1") (pinfunction "1_1") (pintype "passive"))
      (node (ref "C22") (pin "2") (pinfunction "2_2") (pintype "passive"))
      (node (ref "R21") (pin "2") (pinfunction "2_2") (pintype "passive"))
      (node (ref "U$15") (pin "3") (pinfunction "+VS_3") (pintype "bidirectional"))
    )
    (net (code "57") (name "Net-(U$15-BUFIN)") (class "Default")
      (node (ref "U$15") (pin "10") (pinfunction "IOUT_10") (pintype "bidirectional"))
      (node (ref "U$15") (pin "9") (pinfunction "BUFIN_9") (pintype "bidirectional"))
    )
    (net (code "58") (name "Net-(U$15-CAV)") (class "Default")
      (node (ref "C22") (pin "1") (pinfunction "1_1") (pintype "passive"))
      (node (ref "U$15") (pin "6") (pinfunction "CAV_6") (pintype "bidirectional"))
    )
    (net (code "59") (name "Net-(U$15-COM)") (class "Default")
      (node (ref "C20") (pin "1") (pinfunction "1_1") (pintype "passive"))
      (node (ref "R21") (pin "1") (pinfunction "1_1") (pintype "passive"))
      (node (ref "R22") (pin "2") (pinfunction "2_2") (pintype "passive"))
      (node (ref "U$15") (pin "2") (pinfunction "COM_2") (pintype "bidirectional"))
    )
    (net (code "60") (name "Net-(U$15-VIN)") (class "Default")
      (node (ref "C23") (pin "2") (pinfunction "2_2") (pintype "passive"))
      (node (ref "U$15") (pin "4") (pinfunction "VIN_4") (pintype "bidirectional"))
    )
    (net (code "61") (name "Net-(U$17-~{1})") (class "Default")
      (node (ref "U$16") (pin "OUT1") (pinfunction "OUT1_OUT1") (pintype "bidirectional"))
      (node (ref "U$17") (pin "~1") (pinfunction "~{1}_~1") (pintype "bidirectional"))
    )
    (net (code "62") (name "Net-(U$17-~{2})") (class "Default")
      (node (ref "U$16") (pin "OUT2") (pinfunction "OUT2_OUT2") (pintype "bidirectional"))
      (node (ref "U$17") (pin "~2") (pinfunction "~{2}_~2") (pintype "bidirectional"))
    )
    (net (code "63") (name "Net-(U$19-~{1})") (class "Default")
      (node (ref "U$18") (pin "OUT1") (pinfunction "OUT1_OUT1") (pintype "bidirectional"))
      (node (ref "U$19") (pin "~1") (pinfunction "~{1}_~1") (pintype "bidirectional"))
    )
    (net (code "64") (name "Net-(U$19-~{2})") (class "Default")
      (node (ref "U$18") (pin "OUT2") (pinfunction "OUT2_OUT2") (pintype "bidirectional"))
      (node (ref "U$19") (pin "~2") (pinfunction "~{2}_~2") (pintype "bidirectional"))
    )
    (net (code "65") (name "unconnected-(AC1002_1-3-PadP$3)") (class "Default")
      (node (ref "AC1002_1") (pin "P$3") (pinfunction "3_P$3") (pintype "no_connect"))
    )
    (net (code "66") (name "unconnected-(U$1-PadNC)") (class "Default")
      (node (ref "U$1") (pin "NC") (pinfunction "NC_NC") (pintype "bidirectional"))
    )
    (net (code "67") (name "unconnected-(U$1-PadNC1)") (class "Default")
      (node (ref "U$1") (pin "NC1") (pinfunction "NC1_NC1") (pintype "bidirectional"))
    )
    (net (code "68") (name "unconnected-(U$3-CLK-PadSCLOCK)") (class "Default")
      (node (ref "U$3") (pin "SCLOCK") (pinfunction "CLK_SCLOCK") (pintype "bidirectional"))
    )
    (net (code "69") (name "unconnected-(U$3-PadGND2)") (class "Default")
      (node (ref "U$3") (pin "GND2") (pinfunction "GND2_GND2") (pintype "bidirectional"))
    )
    (net (code "70") (name "unconnected-(U$3-PadGND3)") (class "Default")
      (node (ref "U$3") (pin "GND3") (pinfunction "GND3_GND3") (pintype "bidirectional"))
    )
    (net (code "71") (name "unconnected-(U$3-PadMISO)") (class "Default")
      (node (ref "U$3") (pin "MISO") (pinfunction "MISO_MISO") (pintype "bidirectional"))
    )
    (net (code "72") (name "unconnected-(U$3-PadMOSI)") (class "Default")
      (node (ref "U$3") (pin "MOSI") (pinfunction "MOSI_MOSI") (pintype "bidirectional"))
    )
    (net (code "73") (name "unconnected-(U$3-VCC2-PadVCC1)") (class "Default")
      (node (ref "U$3") (pin "VCC1") (pinfunction "VCC2_VCC1") (pintype "bidirectional"))
    )
    (net (code "74") (name "unconnected-(U$4-PadP$1)") (class "Default")
      (node (ref "U$4") (pin "P$1") (pinfunction "P$1_P$1") (pintype "bidirectional"))
    )
    (net (code "75") (name "unconnected-(U$4-PadP$6)") (class "Default")
      (node (ref "U$4") (pin "P$6") (pinfunction "P$6_P$6") (pintype "bidirectional"))
    )
    (net (code "76") (name "unconnected-(U$4-PadP$7)") (class "Default")
      (node (ref "U$4") (pin "P$7") (pinfunction "P$7_P$7") (pintype "bidirectional"))
    )
    (net (code "77") (name "unconnected-(U$4-PadP$8)") (class "Default")
      (node (ref "U$4") (pin "P$8") (pinfunction "P$8_P$8") (pintype "bidirectional"))
    )
    (net (code "78") (name "unconnected-(U$4-PadP$10)") (class "Default")
      (node (ref "U$4") (pin "P$10") (pinfunction "P$10_P$10") (pintype "bidirectional"))
    )
    (net (code "79") (name "unconnected-(U$4-PadP$11)") (class "Default")
      (node (ref "U$4") (pin "P$11") (pinfunction "P$11_P$11") (pintype "bidirectional"))
    )
    (net (code "80") (name "unconnected-(U$4-PadP$12)") (class "Default")
      (node (ref "U$4") (pin "P$12") (pinfunction "P$12_P$12") (pintype "bidirectional"))
    )
    (net (code "81") (name "unconnected-(U$4-PadP$13)") (class "Default")
      (node (ref "U$4") (pin "P$13") (pinfunction "P$13_P$13") (pintype "bidirectional"))
    )
    (net (code "82") (name "unconnected-(U$4-PadP$14)") (class "Default")
      (node (ref "U$4") (pin "P$14") (pinfunction "P$14_P$14") (pintype "bidirectional"))
    )
    (net (code "83") (name "unconnected-(U$4-PadP$15)") (class "Default")
      (node (ref "U$4") (pin "P$15") (pinfunction "P$15_P$15") (pintype "bidirectional"))
    )
    (net (code "84") (name "unconnected-(U$4-PadP$18)") (class "Default")
      (node (ref "U$4") (pin "P$18") (pinfunction "P$18_P$18") (pintype "bidirectional"))
    )
    (net (code "85") (name "unconnected-(U$4-PadP$19)") (class "Default")
      (node (ref "U$4") (pin "P$19") (pinfunction "P$19_P$19") (pintype "bidirectional"))
    )
    (net (code "86") (name "unconnected-(U$4-PadP$22)") (class "Default")
      (node (ref "U$4") (pin "P$22") (pinfunction "P$22_P$22") (pintype "bidirectional"))
    )
    (net (code "87") (name "unconnected-(U$4-PadP$23)") (class "Default")
      (node (ref "U$4") (pin "P$23") (pinfunction "P$23_P$23") (pintype "bidirectional"))
    )
    (net (code "88") (name "unconnected-(U$4-PadP$24)") (class "Default")
      (node (ref "U$4") (pin "P$24") (pinfunction "P$24_P$24") (pintype "bidirectional"))
    )
    (net (code "89") (name "unconnected-(U$4-PadP$26)") (class "Default")
      (node (ref "U$4") (pin "P$26") (pinfunction "P$26_P$26") (pintype "bidirectional"))
    )
    (net (code "90") (name "unconnected-(U$4-PadP$27)") (class "Default")
      (node (ref "U$4") (pin "P$27") (pinfunction "P$27_P$27") (pintype "bidirectional"))
    )
    (net (code "91") (name "unconnected-(U$4-PadP$28)") (class "Default")
      (node (ref "U$4") (pin "P$28") (pinfunction "P$28_P$28") (pintype "bidirectional"))
    )
    (net (code "92") (name "unconnected-(U$4-PadP$29)") (class "Default")
      (node (ref "U$4") (pin "P$29") (pinfunction "P$29_P$29") (pintype "bidirectional"))
    )
    (net (code "93") (name "unconnected-(U$4-PadP$30)") (class "Default")
      (node (ref "U$4") (pin "P$30") (pinfunction "P$30_P$30") (pintype "bidirectional"))
    )
    (net (code "94") (name "unconnected-(U$4-PadP$31)") (class "Default")
      (node (ref "U$4") (pin "P$31") (pinfunction "P$31_P$31") (pintype "bidirectional"))
    )
    (net (code "95") (name "unconnected-(U$7-3-PadP$3)") (class "Default")
      (node (ref "U$7") (pin "P$3") (pinfunction "3_P$3") (pintype "no_connect"))
    )
    (net (code "96") (name "unconnected-(U$12-DB-Pad7)") (class "Default")
      (node (ref "U$12") (pin "7") (pinfunction "DB_7") (pintype "bidirectional"))
    )
    (net (code "97") (name "unconnected-(U$12-RL-Pad1)") (class "Default")
      (node (ref "U$12") (pin "1") (pinfunction "RL_1") (pintype "bidirectional"))
    )
    (net (code "98") (name "unconnected-(U$13-DB-Pad7)") (class "Default")
      (node (ref "U$13") (pin "7") (pinfunction "DB_7") (pintype "bidirectional"))
    )
    (net (code "99") (name "unconnected-(U$13-RL-Pad1)") (class "Default")
      (node (ref "U$13") (pin "1") (pinfunction "RL_1") (pintype "bidirectional"))
    )
    (net (code "100") (name "unconnected-(U$14-3-PadP$3)") (class "Default")
      (node (ref "U$14") (pin "P$3") (pinfunction "3_P$3") (pintype "no_connect"))
    )
    (net (code "101") (name "unconnected-(U$15-DB-Pad7)") (class "Default")
      (node (ref "U$15") (pin "7") (pinfunction "DB_7") (pintype "bidirectional"))
    )
    (net (code "102") (name "unconnected-(U$15-RL-Pad1)") (class "Default")
      (node (ref "U$15") (pin "1") (pinfunction "RL_1") (pintype "bidirectional"))
    )
  )
)
